# gospboard-v3.net
KiCad netlist of a schematic drawn in EAGLE
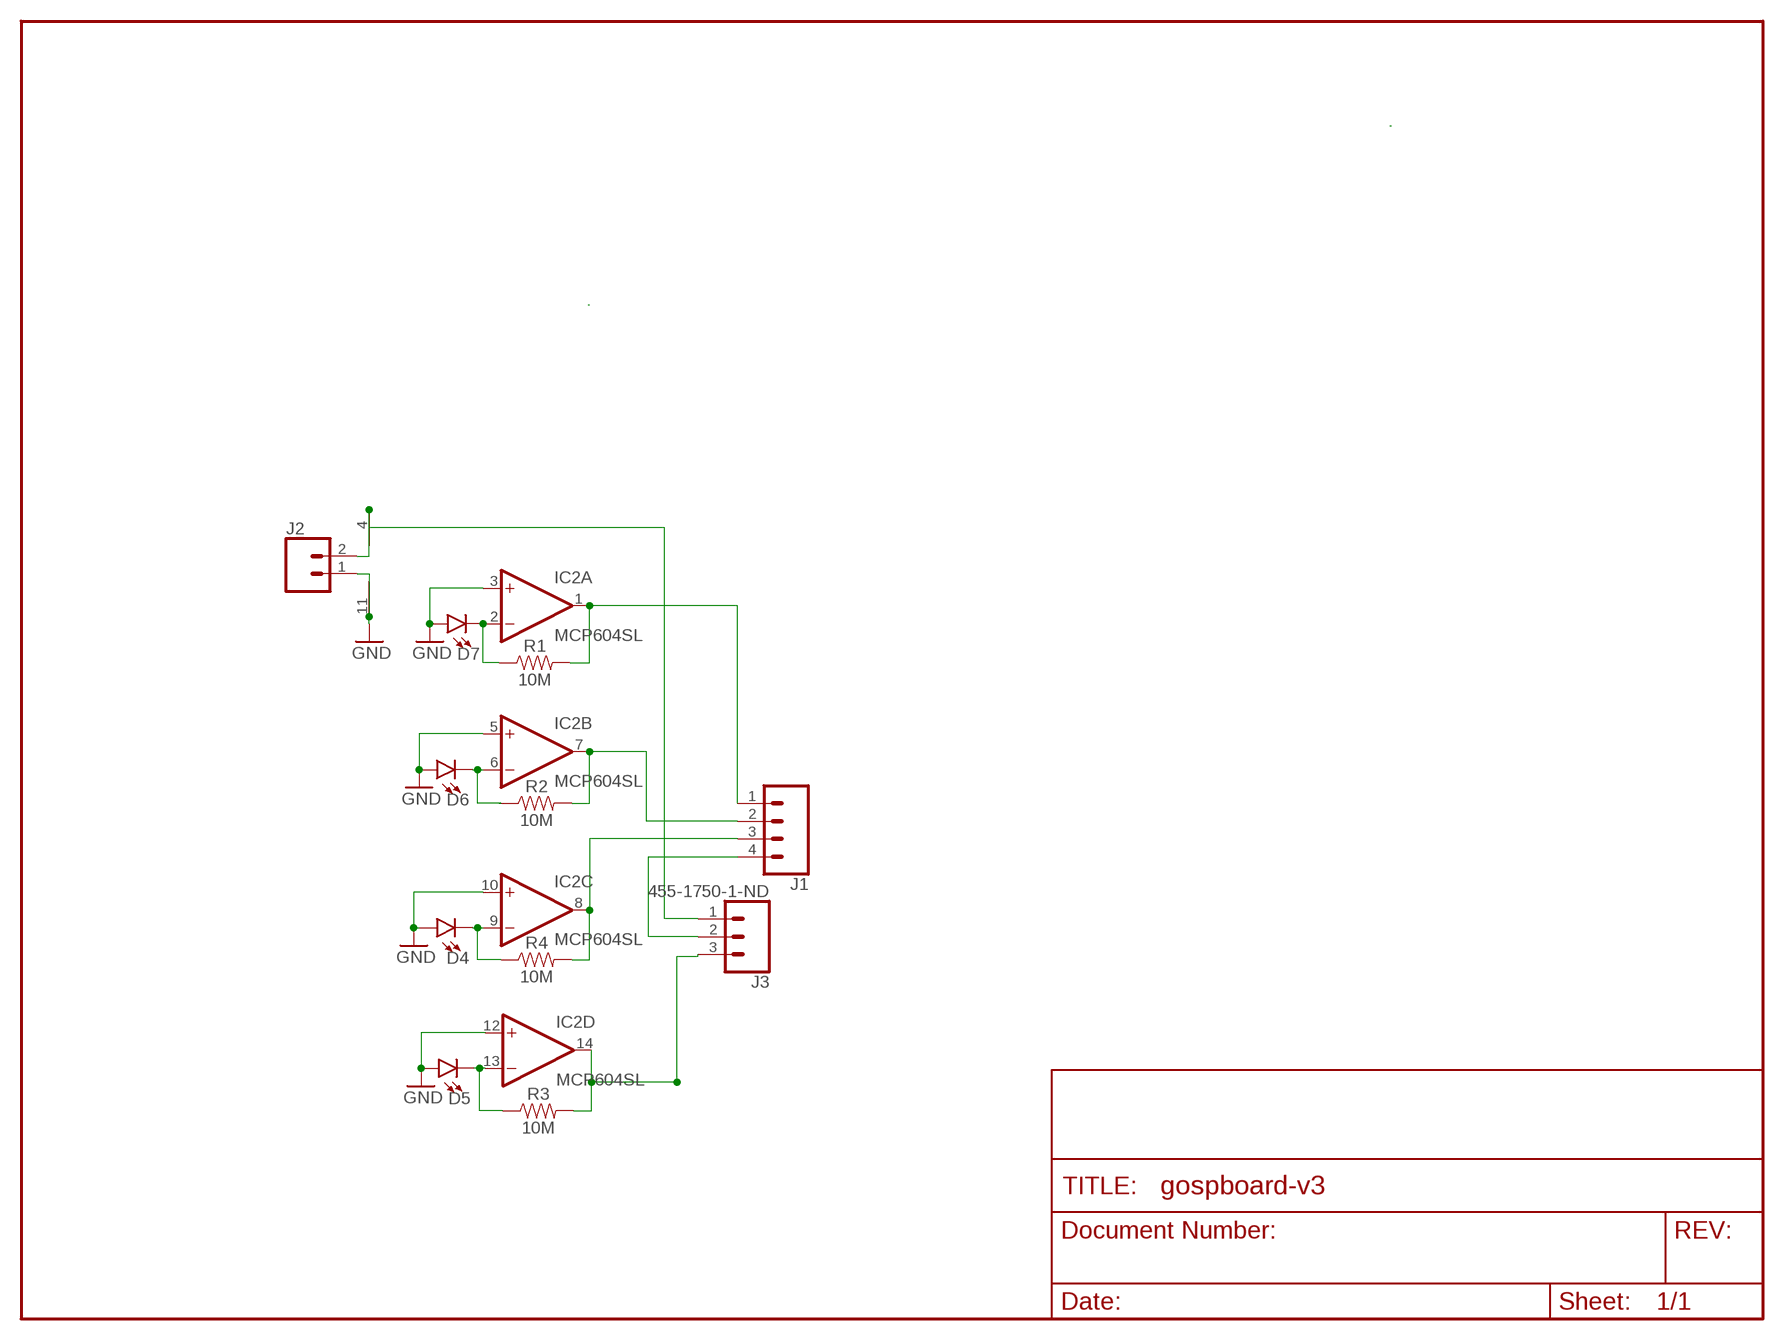
[diagram p0: schematic, sheet 1]

(export (version "E")
  (design (tool "Eeschema 10.0.6"))
  (components
    (comp (ref "D4")
      (value "LED3MM")
      (footprint "eagle-import:LED_3MM")
      (libsource (lib "eagle-import") (part "LED3MM"))
    )
    (comp (ref "D5")
      (value "LED3MM")
      (footprint "eagle-import:LED_3MM")
      (libsource (lib "eagle-import") (part "LED3MM"))
    )
    (comp (ref "D6")
      (value "LED3MM")
      (footprint "eagle-import:LED_3MM")
      (libsource (lib "eagle-import") (part "LED3MM"))
    )
    (comp (ref "D7")
      (value "LED3MM")
      (footprint "eagle-import:LED_3MM")
      (libsource (lib "eagle-import") (part "LED3MM"))
    )
    (comp (ref "IC2")
      (value "MCP604SL")
      (footprint "eagle-import:SO14")
      (libsource (lib "eagle-import") (part "MCP604SL"))
    )
    (comp (ref "J1")
      (value "CONN_04")
      (footprint "eagle-import:1X04")
      (libsource (lib "eagle-import") (part "CONN_04"))
    )
    (comp (ref "J2")
      (value "CONN_02")
      (footprint "eagle-import:1X02")
      (libsource (lib "eagle-import") (part "CONN_02"))
    )
    (comp (ref "J3")
      (value "455-1750-1-ND")
      (footprint "eagle-import:1X03")
      (libsource (lib "eagle-import") (part "CONN_03"))
    )
    (comp (ref "R1")
      (value "10M")
      (footprint "eagle-import:0603")
      (libsource (lib "eagle-import") (part "1MOHM-0603-1/4W-5%"))
    )
    (comp (ref "R2")
      (value "10M")
      (footprint "eagle-import:0603")
      (libsource (lib "eagle-import") (part "1MOHM-0603-1/4W-5%"))
    )
    (comp (ref "R3")
      (value "10M")
      (footprint "eagle-import:0603")
      (libsource (lib "eagle-import") (part "1MOHM-0603-1/4W-5%"))
    )
    (comp (ref "R4")
      (value "10M")
      (footprint "eagle-import:0603")
      (libsource (lib "eagle-import") (part "1MOHM-0603-1/4W-5%"))
    )
  )
  (nets
    (net (code "1") (name "GND") (class "Default")
      (node (ref "D4") (pin "A") (pinfunction "A_A") (pintype "passive"))
      (node (ref "D5") (pin "A") (pinfunction "A_A") (pintype "passive"))
      (node (ref "D6") (pin "A") (pinfunction "A_A") (pintype "passive"))
      (node (ref "D7") (pin "A") (pinfunction "A_A") (pintype "passive"))
      (node (ref "IC2") (pin "10") (pinfunction "+IN_10") (pintype "input"))
      (node (ref "IC2") (pin "11") (pinfunction "V-_11") (pintype "power_in"))
      (node (ref "IC2") (pin "12") (pinfunction "+IN_12") (pintype "input"))
      (node (ref "IC2") (pin "3") (pinfunction "+IN_3") (pintype "input"))
      (node (ref "IC2") (pin "5") (pinfunction "+IN_5") (pintype "input"))
      (node (ref "J2") (pin "1") (pinfunction "1_1") (pintype "passive"))
    )
    (net (code "2") (name "Net-(D4-C)") (class "Default")
      (node (ref "D4") (pin "K") (pinfunction "C_K") (pintype "passive"))
      (node (ref "IC2") (pin "9") (pinfunction "-IN_9") (pintype "input"))
      (node (ref "R4") (pin "1") (pinfunction "1_1") (pintype "passive"))
    )
    (net (code "3") (name "Net-(D5-C)") (class "Default")
      (node (ref "D5") (pin "K") (pinfunction "C_K") (pintype "passive"))
      (node (ref "IC2") (pin "13") (pinfunction "-IN_13") (pintype "input"))
      (node (ref "R3") (pin "1") (pinfunction "1_1") (pintype "passive"))
    )
    (net (code "4") (name "Net-(D6-C)") (class "Default")
      (node (ref "D6") (pin "K") (pinfunction "C_K") (pintype "passive"))
      (node (ref "IC2") (pin "6") (pinfunction "-IN_6") (pintype "input"))
      (node (ref "R2") (pin "1") (pinfunction "1_1") (pintype "passive"))
    )
    (net (code "5") (name "Net-(D7-C)") (class "Default")
      (node (ref "D7") (pin "K") (pinfunction "C_K") (pintype "passive"))
      (node (ref "IC2") (pin "2") (pinfunction "-IN_2") (pintype "input"))
      (node (ref "R1") (pin "1") (pinfunction "1_1") (pintype "passive"))
    )
    (net (code "6") (name "Net-(IC2A-OUT)") (class "Default")
      (node (ref "IC2") (pin "1") (pinfunction "OUT_1") (pintype "output"))
      (node (ref "J1") (pin "1") (pinfunction "1_1") (pintype "passive"))
      (node (ref "R1") (pin "2") (pinfunction "2_2") (pintype "passive"))
    )
    (net (code "7") (name "Net-(IC2B-OUT)") (class "Default")
      (node (ref "IC2") (pin "7") (pinfunction "OUT_7") (pintype "output"))
      (node (ref "J1") (pin "2") (pinfunction "2_2") (pintype "passive"))
      (node (ref "R2") (pin "2") (pinfunction "2_2") (pintype "passive"))
    )
    (net (code "8") (name "Net-(IC2C-OUT)") (class "Default")
      (node (ref "IC2") (pin "8") (pinfunction "OUT_8") (pintype "output"))
      (node (ref "J1") (pin "3") (pinfunction "3_3") (pintype "passive"))
      (node (ref "R4") (pin "2") (pinfunction "2_2") (pintype "passive"))
    )
    (net (code "9") (name "Net-(IC2D-OUT)") (class "Default")
      (node (ref "IC2") (pin "14") (pinfunction "OUT_14") (pintype "output"))
      (node (ref "J3") (pin "3") (pinfunction "3_3") (pintype "passive"))
      (node (ref "R3") (pin "2") (pinfunction "2_2") (pintype "passive"))
    )
    (net (code "10") (name "Net-(IC2E-V+)") (class "Default")
      (node (ref "IC2") (pin "4") (pinfunction "V+_4") (pintype "power_in"))
      (node (ref "J2") (pin "2") (pinfunction "2_2") (pintype "passive"))
      (node (ref "J3") (pin "1") (pinfunction "1_1") (pintype "passive"))
    )
    (net (code "11") (name "Net-(J1-Pad4)") (class "Default")
      (node (ref "J1") (pin "4") (pinfunction "4_4") (pintype "passive"))
      (node (ref "J3") (pin "2") (pinfunction "2_2") (pintype "passive"))
    )
  )
)
